# Charger_Board_3.net
KiCad netlist of a schematic drawn in EAGLE
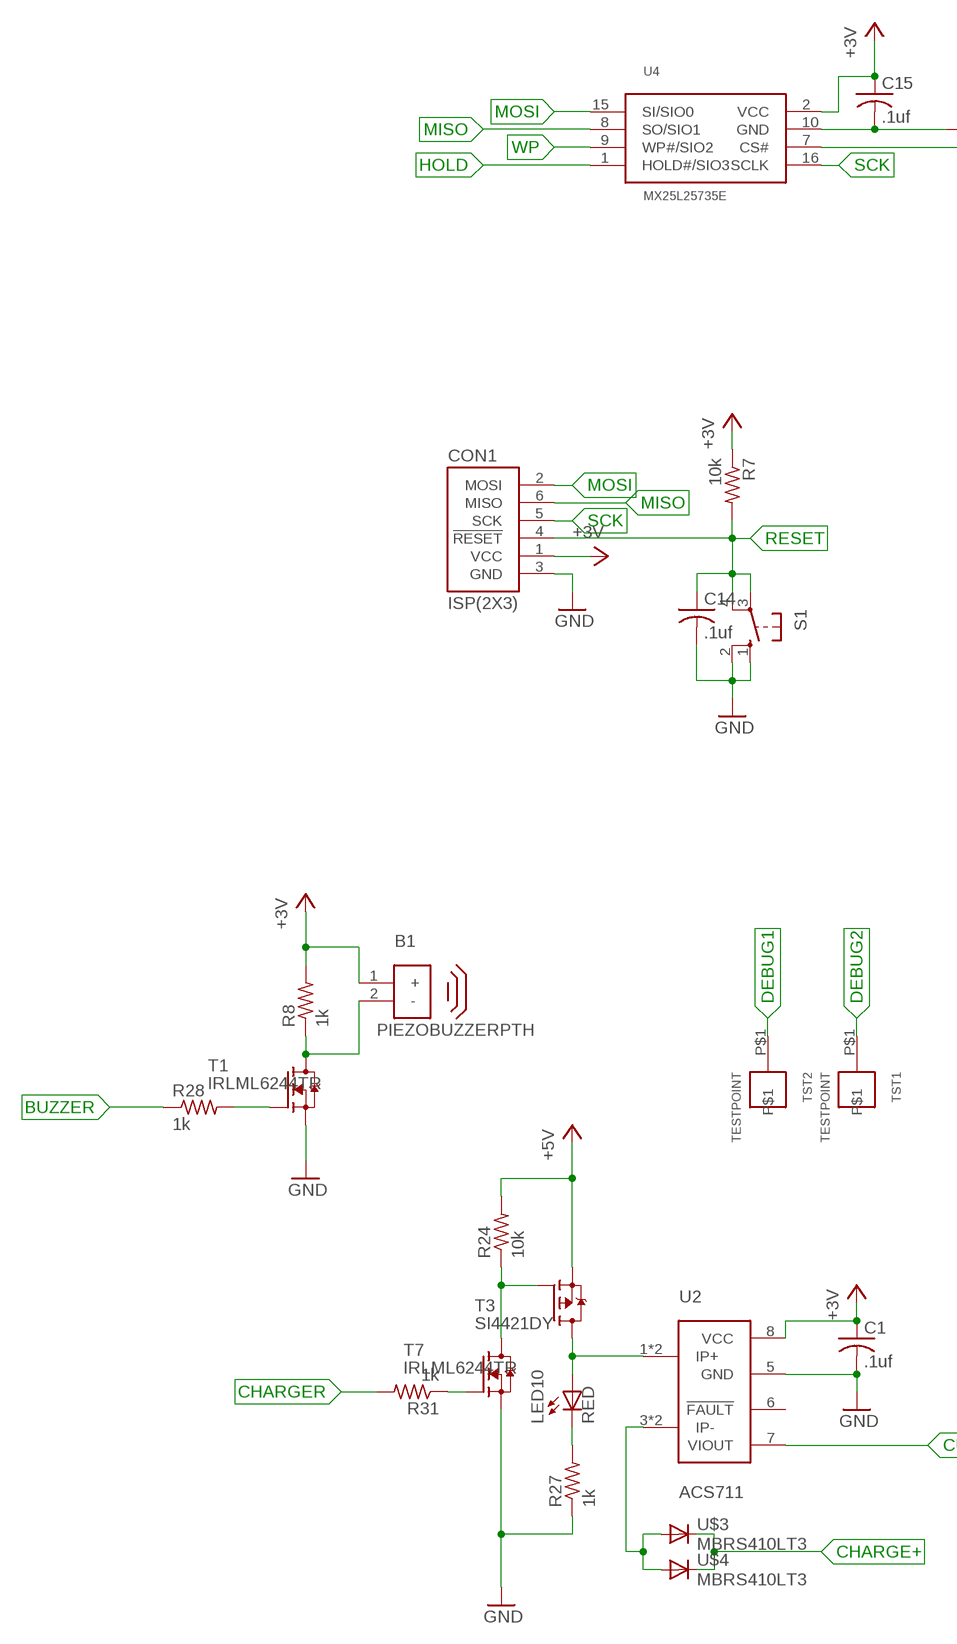
[diagram p0: schematic, sheet 1, part 1 of 2]
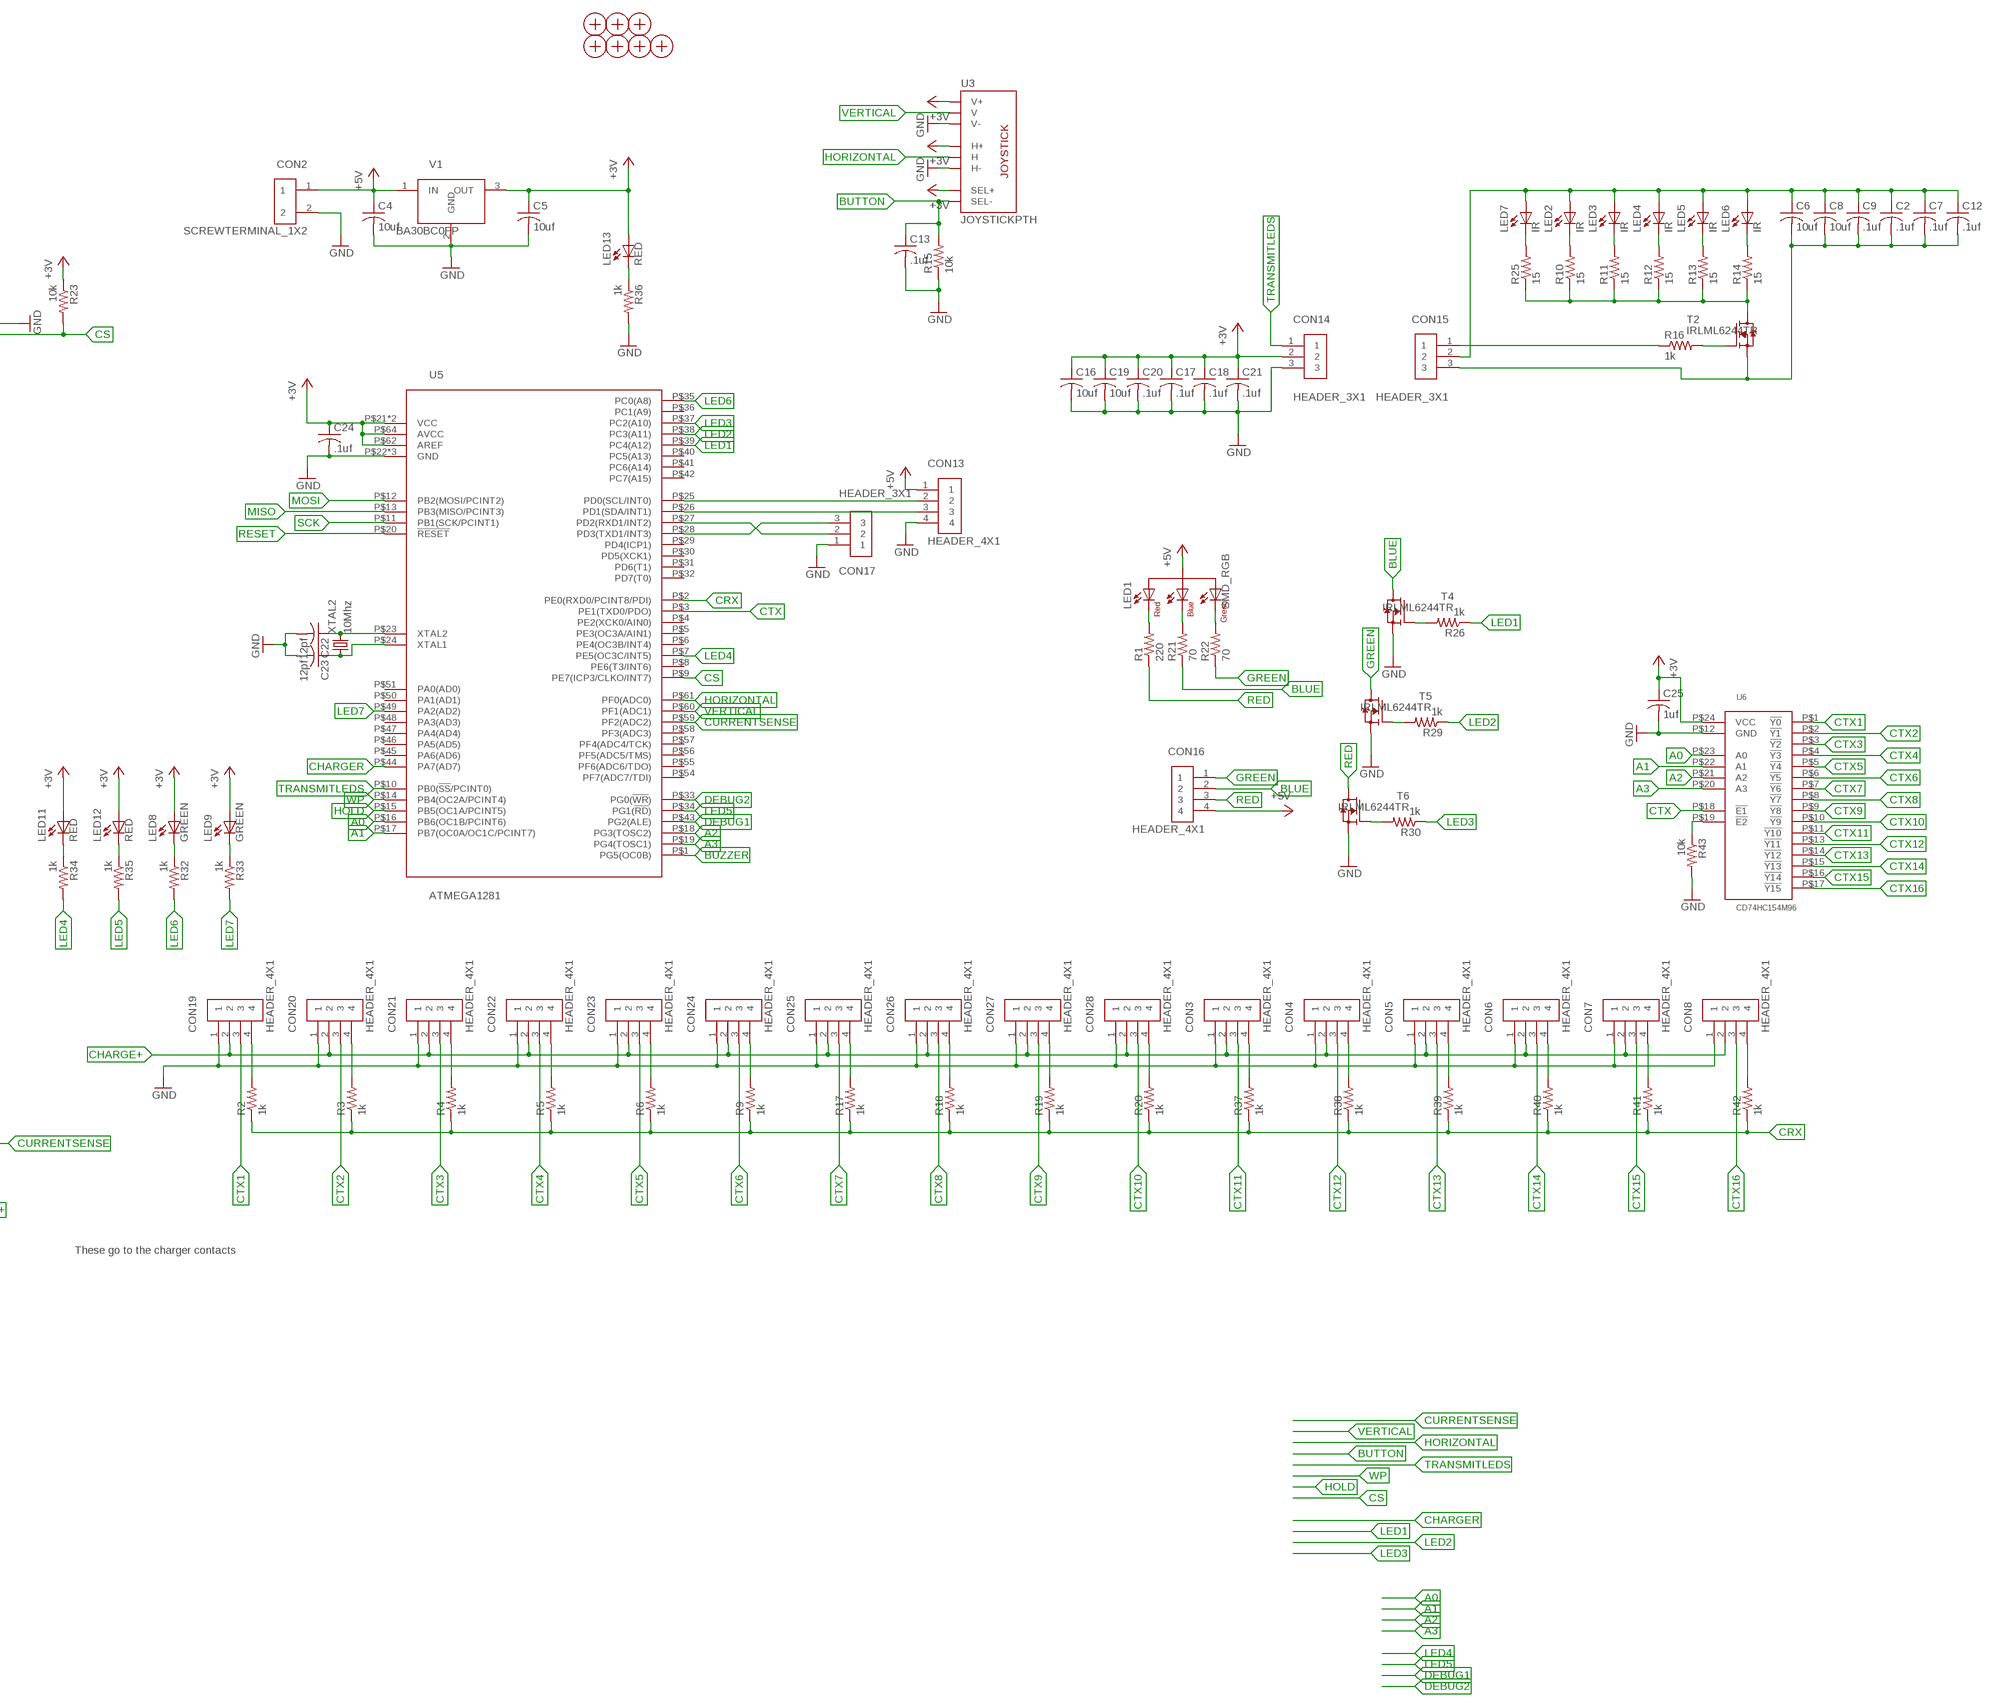
[diagram p1: schematic, sheet 1, part 2 of 2]

(export (version "E")
  (design (tool "Eeschema 10.0.6"))
  (components
    (comp (ref "B1")
      (value "PIEZOBUZZERPTH")
      (footprint "eagle-import:PIEZOBUZZER")
      (libsource (lib "eagle-import") (part "PIEZOBUZZERPTH"))
    )
    (comp (ref "C1")
      (value ".1uf")
      (footprint "eagle-import:0603")
      (libsource (lib "eagle-import") (part "CAP0603"))
    )
    (comp (ref "C2")
      (value ".1uf")
      (footprint "eagle-import:0603")
      (libsource (lib "eagle-import") (part "CAP0603"))
    )
    (comp (ref "C4")
      (value "10uf")
      (footprint "eagle-import:0805")
      (libsource (lib "eagle-import") (part "CAP0805"))
    )
    (comp (ref "C5")
      (value "10uf")
      (footprint "eagle-import:0805")
      (libsource (lib "eagle-import") (part "CAP0805"))
    )
    (comp (ref "C6")
      (value "10uf")
      (footprint "eagle-import:0805")
      (libsource (lib "eagle-import") (part "CAP0805"))
    )
    (comp (ref "C7")
      (value ".1uf")
      (footprint "eagle-import:0603")
      (libsource (lib "eagle-import") (part "CAP0603"))
    )
    (comp (ref "C8")
      (value "10uf")
      (footprint "eagle-import:0805")
      (libsource (lib "eagle-import") (part "CAP0805"))
    )
    (comp (ref "C9")
      (value ".1uf")
      (footprint "eagle-import:0603")
      (libsource (lib "eagle-import") (part "CAP0603"))
    )
    (comp (ref "C12")
      (value ".1uf")
      (footprint "eagle-import:0603")
      (libsource (lib "eagle-import") (part "CAP0603"))
    )
    (comp (ref "C13")
      (value ".1uf")
      (footprint "eagle-import:0603")
      (libsource (lib "eagle-import") (part "CAP0603"))
    )
    (comp (ref "C14")
      (value ".1uf")
      (footprint "eagle-import:0603")
      (libsource (lib "eagle-import") (part "CAP0603"))
    )
    (comp (ref "C15")
      (value ".1uf")
      (footprint "eagle-import:0603")
      (libsource (lib "eagle-import") (part "CAP0603"))
    )
    (comp (ref "C16")
      (value "10uf")
      (footprint "eagle-import:0805")
      (libsource (lib "eagle-import") (part "CAP0805"))
    )
    (comp (ref "C17")
      (value ".1uf")
      (footprint "eagle-import:0603")
      (libsource (lib "eagle-import") (part "CAP0603"))
    )
    (comp (ref "C18")
      (value ".1uf")
      (footprint "eagle-import:0603")
      (libsource (lib "eagle-import") (part "CAP0603"))
    )
    (comp (ref "C19")
      (value "10uf")
      (footprint "eagle-import:0805")
      (libsource (lib "eagle-import") (part "CAP0805"))
    )
    (comp (ref "C20")
      (value ".1uf")
      (footprint "eagle-import:0603")
      (libsource (lib "eagle-import") (part "CAP0603"))
    )
    (comp (ref "C21")
      (value ".1uf")
      (footprint "eagle-import:0603")
      (libsource (lib "eagle-import") (part "CAP0603"))
    )
    (comp (ref "C22")
      (value "12pf")
      (footprint "eagle-import:0603")
      (libsource (lib "eagle-import") (part "CAP0603"))
    )
    (comp (ref "C23")
      (value "12pf")
      (footprint "eagle-import:0603")
      (libsource (lib "eagle-import") (part "CAP0603"))
    )
    (comp (ref "C24")
      (value ".1uf")
      (footprint "eagle-import:0603")
      (libsource (lib "eagle-import") (part "CAP0603"))
    )
    (comp (ref "C25")
      (value "1uf")
      (footprint "eagle-import:0603")
      (libsource (lib "eagle-import") (part "CAP0603"))
    )
    (comp (ref "CON1")
      (value "ISP(2X3)")
      (footprint "eagle-import:PINHEADER(2X3)")
      (libsource (lib "eagle-import") (part "ISP(2X3)"))
    )
    (comp (ref "CON2")
      (value "SCREWTERMINAL_1X2")
      (footprint "eagle-import:SCREWTERMINAL_1X2")
      (libsource (lib "eagle-import") (part "SCREWTERMINAL_1X2"))
    )
    (comp (ref "CON3")
      (value "HEADER_4X1")
      (footprint "eagle-import:4PINHEADER_.100_")
      (libsource (lib "eagle-import") (part "HEADER_4X1"))
    )
    (comp (ref "CON4")
      (value "HEADER_4X1")
      (footprint "eagle-import:4PINHEADER_.100_")
      (libsource (lib "eagle-import") (part "HEADER_4X1"))
    )
    (comp (ref "CON5")
      (value "HEADER_4X1")
      (footprint "eagle-import:4PINHEADER_.100_")
      (libsource (lib "eagle-import") (part "HEADER_4X1"))
    )
    (comp (ref "CON6")
      (value "HEADER_4X1")
      (footprint "eagle-import:4PINHEADER_.100_")
      (libsource (lib "eagle-import") (part "HEADER_4X1"))
    )
    (comp (ref "CON7")
      (value "HEADER_4X1")
      (footprint "eagle-import:4PINHEADER_.100_")
      (libsource (lib "eagle-import") (part "HEADER_4X1"))
    )
    (comp (ref "CON8")
      (value "HEADER_4X1")
      (footprint "eagle-import:4PINHEADER_.100_")
      (libsource (lib "eagle-import") (part "HEADER_4X1"))
    )
    (comp (ref "CON13")
      (value "HEADER_4X1")
      (footprint "eagle-import:4PINHEADER_.100_")
      (libsource (lib "eagle-import") (part "HEADER_4X1"))
    )
    (comp (ref "CON14")
      (value "HEADER_3X1")
      (footprint "eagle-import:3PINHEADER_.100_")
      (libsource (lib "eagle-import") (part "HEADER_3X1"))
    )
    (comp (ref "CON15")
      (value "HEADER_3X1")
      (footprint "eagle-import:3PINHEADER_.100_")
      (libsource (lib "eagle-import") (part "HEADER_3X1"))
    )
    (comp (ref "CON16")
      (value "HEADER_4X1")
      (footprint "eagle-import:4PINHEADER_.100_")
      (libsource (lib "eagle-import") (part "HEADER_4X1"))
    )
    (comp (ref "CON17")
      (value "HEADER_3X1")
      (footprint "eagle-import:3PINHEADER_.100_")
      (libsource (lib "eagle-import") (part "HEADER_3X1"))
    )
    (comp (ref "CON19")
      (value "HEADER_4X1")
      (footprint "eagle-import:4PINHEADER_.100_")
      (libsource (lib "eagle-import") (part "HEADER_4X1"))
    )
    (comp (ref "CON20")
      (value "HEADER_4X1")
      (footprint "eagle-import:4PINHEADER_.100_")
      (libsource (lib "eagle-import") (part "HEADER_4X1"))
    )
    (comp (ref "CON21")
      (value "HEADER_4X1")
      (footprint "eagle-import:4PINHEADER_.100_")
      (libsource (lib "eagle-import") (part "HEADER_4X1"))
    )
    (comp (ref "CON22")
      (value "HEADER_4X1")
      (footprint "eagle-import:4PINHEADER_.100_")
      (libsource (lib "eagle-import") (part "HEADER_4X1"))
    )
    (comp (ref "CON23")
      (value "HEADER_4X1")
      (footprint "eagle-import:4PINHEADER_.100_")
      (libsource (lib "eagle-import") (part "HEADER_4X1"))
    )
    (comp (ref "CON24")
      (value "HEADER_4X1")
      (footprint "eagle-import:4PINHEADER_.100_")
      (libsource (lib "eagle-import") (part "HEADER_4X1"))
    )
    (comp (ref "CON25")
      (value "HEADER_4X1")
      (footprint "eagle-import:4PINHEADER_.100_")
      (libsource (lib "eagle-import") (part "HEADER_4X1"))
    )
    (comp (ref "CON26")
      (value "HEADER_4X1")
      (footprint "eagle-import:4PINHEADER_.100_")
      (libsource (lib "eagle-import") (part "HEADER_4X1"))
    )
    (comp (ref "CON27")
      (value "HEADER_4X1")
      (footprint "eagle-import:4PINHEADER_.100_")
      (libsource (lib "eagle-import") (part "HEADER_4X1"))
    )
    (comp (ref "CON28")
      (value "HEADER_4X1")
      (footprint "eagle-import:4PINHEADER_.100_")
      (libsource (lib "eagle-import") (part "HEADER_4X1"))
    )
    (comp (ref "H1")
      (value "MOUNTINGHOLE")
      (footprint "eagle-import:MOUNTINGHOLE")
      (libsource (lib "eagle-import") (part "MOUNTINGHOLE"))
    )
    (comp (ref "H2")
      (value "MOUNTINGHOLE")
      (footprint "eagle-import:MOUNTINGHOLE")
      (libsource (lib "eagle-import") (part "MOUNTINGHOLE"))
    )
    (comp (ref "H3")
      (value "MOUNTINGHOLE")
      (footprint "eagle-import:MOUNTINGHOLE")
      (libsource (lib "eagle-import") (part "MOUNTINGHOLE"))
    )
    (comp (ref "H4")
      (value "MOUNTINGHOLE")
      (footprint "eagle-import:MOUNTINGHOLE")
      (libsource (lib "eagle-import") (part "MOUNTINGHOLE"))
    )
    (comp (ref "H5")
      (value "MOUNTINGHOLE")
      (footprint "eagle-import:MOUNTINGHOLE")
      (libsource (lib "eagle-import") (part "MOUNTINGHOLE"))
    )
    (comp (ref "H6")
      (value "MOUNTINGHOLE")
      (footprint "eagle-import:MOUNTINGHOLE")
      (libsource (lib "eagle-import") (part "MOUNTINGHOLE"))
    )
    (comp (ref "H7")
      (value "MOUNTINGHOLE")
      (footprint "eagle-import:MOUNTINGHOLE")
      (libsource (lib "eagle-import") (part "MOUNTINGHOLE"))
    )
    (comp (ref "LED1")
      (value "SMD_RGB")
      (footprint "eagle-import:PLCC4")
      (libsource (lib "eagle-import") (part "SMD_RGB"))
    )
    (comp (ref "LED2")
      (value "IR")
      (footprint "eagle-import:5MM_LED_RA")
      (libsource (lib "eagle-import") (part "LED5MMRA"))
    )
    (comp (ref "LED3")
      (value "IR")
      (footprint "eagle-import:5MM_LED_RA")
      (libsource (lib "eagle-import") (part "LED5MMRA"))
    )
    (comp (ref "LED4")
      (value "IR")
      (footprint "eagle-import:5MM_LED_RA")
      (libsource (lib "eagle-import") (part "LED5MMRA"))
    )
    (comp (ref "LED5")
      (value "IR")
      (footprint "eagle-import:5MM_LED_RA")
      (libsource (lib "eagle-import") (part "LED5MMRA"))
    )
    (comp (ref "LED6")
      (value "IR")
      (footprint "eagle-import:5MM_LED_RA")
      (libsource (lib "eagle-import") (part "LED5MMRA"))
    )
    (comp (ref "LED7")
      (value "IR")
      (footprint "eagle-import:5MM_LED_RA")
      (libsource (lib "eagle-import") (part "LED5MMRA"))
    )
    (comp (ref "LED8")
      (value "GREEN")
      (footprint "eagle-import:LED0603")
      (libsource (lib "eagle-import") (part "LED0603"))
    )
    (comp (ref "LED9")
      (value "GREEN")
      (footprint "eagle-import:LED0603")
      (libsource (lib "eagle-import") (part "LED0603"))
    )
    (comp (ref "LED10")
      (value "RED")
      (footprint "eagle-import:LED0603")
      (libsource (lib "eagle-import") (part "LED0603"))
    )
    (comp (ref "LED11")
      (value "RED")
      (footprint "eagle-import:LED0603")
      (libsource (lib "eagle-import") (part "LED0603"))
    )
    (comp (ref "LED12")
      (value "RED")
      (footprint "eagle-import:LED0603")
      (libsource (lib "eagle-import") (part "LED0603"))
    )
    (comp (ref "LED13")
      (value "RED")
      (footprint "eagle-import:LED0603")
      (libsource (lib "eagle-import") (part "LED0603"))
    )
    (comp (ref "R1")
      (value "220")
      (footprint "eagle-import:0603")
      (libsource (lib "eagle-import") (part "RES0603"))
    )
    (comp (ref "R2")
      (value "1k")
      (footprint "eagle-import:0603")
      (libsource (lib "eagle-import") (part "RES0603"))
    )
    (comp (ref "R3")
      (value "1k")
      (footprint "eagle-import:0603")
      (libsource (lib "eagle-import") (part "RES0603"))
    )
    (comp (ref "R4")
      (value "1k")
      (footprint "eagle-import:0603")
      (libsource (lib "eagle-import") (part "RES0603"))
    )
    (comp (ref "R5")
      (value "1k")
      (footprint "eagle-import:0603")
      (libsource (lib "eagle-import") (part "RES0603"))
    )
    (comp (ref "R6")
      (value "1k")
      (footprint "eagle-import:0603")
      (libsource (lib "eagle-import") (part "RES0603"))
    )
    (comp (ref "R7")
      (value "10k")
      (footprint "eagle-import:0603")
      (libsource (lib "eagle-import") (part "RES0603"))
    )
    (comp (ref "R8")
      (value "1k")
      (footprint "eagle-import:0603")
      (libsource (lib "eagle-import") (part "RES0603"))
    )
    (comp (ref "R9")
      (value "1k")
      (footprint "eagle-import:0603")
      (libsource (lib "eagle-import") (part "RES0603"))
    )
    (comp (ref "R10")
      (value "15")
      (footprint "eagle-import:0603")
      (libsource (lib "eagle-import") (part "RES0603"))
    )
    (comp (ref "R11")
      (value "15")
      (footprint "eagle-import:0603")
      (libsource (lib "eagle-import") (part "RES0603"))
    )
    (comp (ref "R12")
      (value "15")
      (footprint "eagle-import:0603")
      (libsource (lib "eagle-import") (part "RES0603"))
    )
    (comp (ref "R13")
      (value "15")
      (footprint "eagle-import:0603")
      (libsource (lib "eagle-import") (part "RES0603"))
    )
    (comp (ref "R14")
      (value "15")
      (footprint "eagle-import:0603")
      (libsource (lib "eagle-import") (part "RES0603"))
    )
    (comp (ref "R15")
      (value "10k")
      (footprint "eagle-import:0603")
      (libsource (lib "eagle-import") (part "RES0603"))
    )
    (comp (ref "R16")
      (value "1k")
      (footprint "eagle-import:0603")
      (libsource (lib "eagle-import") (part "RES0603"))
    )
    (comp (ref "R17")
      (value "1k")
      (footprint "eagle-import:0603")
      (libsource (lib "eagle-import") (part "RES0603"))
    )
    (comp (ref "R18")
      (value "1k")
      (footprint "eagle-import:0603")
      (libsource (lib "eagle-import") (part "RES0603"))
    )
    (comp (ref "R19")
      (value "1k")
      (footprint "eagle-import:0603")
      (libsource (lib "eagle-import") (part "RES0603"))
    )
    (comp (ref "R20")
      (value "1k")
      (footprint "eagle-import:0603")
      (libsource (lib "eagle-import") (part "RES0603"))
    )
    (comp (ref "R21")
      (value "70")
      (footprint "eagle-import:0603")
      (libsource (lib "eagle-import") (part "RES0603"))
    )
    (comp (ref "R22")
      (value "70")
      (footprint "eagle-import:0603")
      (libsource (lib "eagle-import") (part "RES0603"))
    )
    (comp (ref "R23")
      (value "10k")
      (footprint "eagle-import:0603")
      (libsource (lib "eagle-import") (part "RES0603"))
    )
    (comp (ref "R24")
      (value "10k")
      (footprint "eagle-import:0603")
      (libsource (lib "eagle-import") (part "RES0603"))
    )
    (comp (ref "R25")
      (value "15")
      (footprint "eagle-import:0603")
      (libsource (lib "eagle-import") (part "RES0603"))
    )
    (comp (ref "R26")
      (value "1k")
      (footprint "eagle-import:0603")
      (libsource (lib "eagle-import") (part "RES0603"))
    )
    (comp (ref "R27")
      (value "1k")
      (footprint "eagle-import:0603")
      (libsource (lib "eagle-import") (part "RES0603"))
    )
    (comp (ref "R28")
      (value "1k")
      (footprint "eagle-import:0603")
      (libsource (lib "eagle-import") (part "RES0603"))
    )
    (comp (ref "R29")
      (value "1k")
      (footprint "eagle-import:0603")
      (libsource (lib "eagle-import") (part "RES0603"))
    )
    (comp (ref "R30")
      (value "1k")
      (footprint "eagle-import:0603")
      (libsource (lib "eagle-import") (part "RES0603"))
    )
    (comp (ref "R31")
      (value "1k")
      (footprint "eagle-import:0603")
      (libsource (lib "eagle-import") (part "RES0603"))
    )
    (comp (ref "R32")
      (value "1k")
      (footprint "eagle-import:0603")
      (libsource (lib "eagle-import") (part "RES0603"))
    )
    (comp (ref "R33")
      (value "1k")
      (footprint "eagle-import:0603")
      (libsource (lib "eagle-import") (part "RES0603"))
    )
    (comp (ref "R34")
      (value "1k")
      (footprint "eagle-import:0603")
      (libsource (lib "eagle-import") (part "RES0603"))
    )
    (comp (ref "R35")
      (value "1k")
      (footprint "eagle-import:0603")
      (libsource (lib "eagle-import") (part "RES0603"))
    )
    (comp (ref "R36")
      (value "1k")
      (footprint "eagle-import:0603")
      (libsource (lib "eagle-import") (part "RES0603"))
    )
    (comp (ref "R37")
      (value "1k")
      (footprint "eagle-import:0603")
      (libsource (lib "eagle-import") (part "RES0603"))
    )
    (comp (ref "R38")
      (value "1k")
      (footprint "eagle-import:0603")
      (libsource (lib "eagle-import") (part "RES0603"))
    )
    (comp (ref "R39")
      (value "1k")
      (footprint "eagle-import:0603")
      (libsource (lib "eagle-import") (part "RES0603"))
    )
    (comp (ref "R40")
      (value "1k")
      (footprint "eagle-import:0603")
      (libsource (lib "eagle-import") (part "RES0603"))
    )
    (comp (ref "R41")
      (value "1k")
      (footprint "eagle-import:0603")
      (libsource (lib "eagle-import") (part "RES0603"))
    )
    (comp (ref "R42")
      (value "1k")
      (footprint "eagle-import:0603")
      (libsource (lib "eagle-import") (part "RES0603"))
    )
    (comp (ref "R43")
      (value "10k")
      (footprint "eagle-import:0603")
      (libsource (lib "eagle-import") (part "RES0603"))
    )
    (comp (ref "S1")
      (value "10-XX")
      (footprint "eagle-import:B3F-10XX")
      (fields (field (name "MPN") "B3F-1000"))
      (libsource (lib "eagle-import") (part "10-XX"))
    )
    (comp (ref "T1")
      (value "IRLML6244TR")
      (footprint "eagle-import:SOT23")
      (libsource (lib "eagle-import") (part "IRLML6244TR"))
    )
    (comp (ref "T2")
      (value "IRLML6244TR")
      (footprint "eagle-import:SOT23")
      (libsource (lib "eagle-import") (part "IRLML6244TR"))
    )
    (comp (ref "T3")
      (value "SI4421DY")
      (footprint "eagle-import:S0-8")
      (libsource (lib "eagle-import") (part "SI4421DY"))
    )
    (comp (ref "T4")
      (value "IRLML6244TR")
      (footprint "eagle-import:SOT23")
      (libsource (lib "eagle-import") (part "IRLML6244TR"))
    )
    (comp (ref "T5")
      (value "IRLML6244TR")
      (footprint "eagle-import:SOT23")
      (libsource (lib "eagle-import") (part "IRLML6244TR"))
    )
    (comp (ref "T6")
      (value "IRLML6244TR")
      (footprint "eagle-import:SOT23")
      (libsource (lib "eagle-import") (part "IRLML6244TR"))
    )
    (comp (ref "T7")
      (value "IRLML6244TR")
      (footprint "eagle-import:SOT23")
      (libsource (lib "eagle-import") (part "IRLML6244TR"))
    )
    (comp (ref "TST1")
      (value "TESTPOINT")
      (footprint "eagle-import:TESTPOINT")
      (libsource (lib "eagle-import") (part "TESTPOINT"))
    )
    (comp (ref "TST2")
      (value "TESTPOINT")
      (footprint "eagle-import:TESTPOINT")
      (libsource (lib "eagle-import") (part "TESTPOINT"))
    )
    (comp (ref "U$3")
      (value "MBRS410LT3")
      (footprint "eagle-import:SMD_DIODE")
      (libsource (lib "eagle-import") (part "MBRS410LT3"))
    )
    (comp (ref "U$4")
      (value "MBRS410LT3")
      (footprint "eagle-import:SMD_DIODE")
      (libsource (lib "eagle-import") (part "MBRS410LT3"))
    )
    (comp (ref "U2")
      (value "ACS711")
      (footprint "eagle-import:8SOIC")
      (libsource (lib "eagle-import") (part "ACS711"))
    )
    (comp (ref "U3")
      (value "JOYSTICKPTH")
      (footprint "eagle-import:JOYSTICK")
      (libsource (lib "eagle-import") (part "JOYSTICKPTH"))
    )
    (comp (ref "U4")
      (value "MX25L25735E")
      (footprint "eagle-import:SOIC16R")
      (libsource (lib "eagle-import") (part "MX25L25735E"))
    )
    (comp (ref "U5")
      (value "ATMEGA1281")
      (footprint "eagle-import:TQFP64")
      (libsource (lib "eagle-import") (part "ATMEGA1281"))
    )
    (comp (ref "U6")
      (value "CD74HC154M96")
      (footprint "eagle-import:24SOIC")
      (libsource (lib "eagle-import") (part "CD74HC154M96"))
    )
    (comp (ref "V1")
      (value "BA30BC0FP")
      (footprint "eagle-import:DPAK")
      (libsource (lib "eagle-import") (part "BA30BC0FP"))
    )
    (comp (ref "XTAL2")
      (value "10Mhz")
      (footprint "eagle-import:SMDXTAL")
      (libsource (lib "eagle-import") (part "NX5032GA-10.000000MHZ"))
    )
  )
  (nets
    (net (code "1") (name "+3V") (class "Default")
      (node (ref "B1") (pin "1") (pinfunction "+_1") (pintype "bidirectional"))
      (node (ref "C1") (pin "1") (pinfunction "1_1") (pintype "passive"))
      (node (ref "C15") (pin "1") (pinfunction "1_1") (pintype "passive"))
      (node (ref "C16") (pin "1") (pinfunction "1_1") (pintype "passive"))
      (node (ref "C17") (pin "1") (pinfunction "1_1") (pintype "passive"))
      (node (ref "C18") (pin "1") (pinfunction "1_1") (pintype "passive"))
      (node (ref "C19") (pin "1") (pinfunction "1_1") (pintype "passive"))
      (node (ref "C20") (pin "1") (pinfunction "1_1") (pintype "passive"))
      (node (ref "C21") (pin "1") (pinfunction "1_1") (pintype "passive"))
      (node (ref "C24") (pin "1") (pinfunction "1_1") (pintype "passive"))
      (node (ref "C25") (pin "1") (pinfunction "1_1") (pintype "passive"))
      (node (ref "C5") (pin "1") (pinfunction "1_1") (pintype "passive"))
      (node (ref "CON1") (pin "1") (pinfunction "VCC_1") (pintype "bidirectional"))
      (node (ref "CON14") (pin "2") (pinfunction "2_2") (pintype "bidirectional"))
      (node (ref "LED11") (pin "2") (pinfunction "A_2") (pintype "passive"))
      (node (ref "LED12") (pin "2") (pinfunction "A_2") (pintype "passive"))
      (node (ref "LED13") (pin "2") (pinfunction "A_2") (pintype "passive"))
      (node (ref "LED8") (pin "2") (pinfunction "A_2") (pintype "passive"))
      (node (ref "LED9") (pin "2") (pinfunction "A_2") (pintype "passive"))
      (node (ref "R23") (pin "1") (pinfunction "1_1") (pintype "passive"))
      (node (ref "R7") (pin "1") (pinfunction "1_1") (pintype "passive"))
      (node (ref "R8") (pin "2") (pinfunction "2_2") (pintype "passive"))
      (node (ref "U2") (pin "8") (pinfunction "VCC_8") (pintype "bidirectional"))
      (node (ref "U3") (pin "B1A") (pinfunction "SEL+_B1A") (pintype "bidirectional"))
      (node (ref "U3") (pin "H1") (pinfunction "H+_H1") (pintype "bidirectional"))
      (node (ref "U3") (pin "V1") (pinfunction "V+_V1") (pintype "bidirectional"))
      (node (ref "U4") (pin "2") (pinfunction "VCC_2") (pintype "bidirectional"))
      (node (ref "U5") (pin "P$21") (pinfunction "VCC_P$21") (pintype "bidirectional"))
      (node (ref "U5") (pin "P$52") (pinfunction "VCC_P$52") (pintype "bidirectional"))
      (node (ref "U5") (pin "P$62") (pinfunction "AREF_P$62") (pintype "bidirectional"))
      (node (ref "U5") (pin "P$64") (pinfunction "AVCC_P$64") (pintype "bidirectional"))
      (node (ref "U6") (pin "P$24") (pinfunction "VCC_P$24") (pintype "bidirectional"))
      (node (ref "V1") (pin "3") (pinfunction "OUT_3") (pintype "bidirectional"))
    )
    (net (code "2") (name "+5V") (class "Default")
      (node (ref "C4") (pin "1") (pinfunction "1_1") (pintype "passive"))
      (node (ref "CON13") (pin "1") (pinfunction "1_1") (pintype "bidirectional"))
      (node (ref "CON16") (pin "4") (pinfunction "4_4") (pintype "bidirectional"))
      (node (ref "CON2") (pin "1") (pinfunction "1_1") (pintype "bidirectional"))
      (node (ref "LED1") (pin "2") (pinfunction "COMMONANODE_2") (pintype "passive"))
      (node (ref "R24") (pin "2") (pinfunction "2_2") (pintype "passive"))
      (node (ref "T3") (pin "1") (pinfunction "S_1") (pintype "passive"))
      (node (ref "T3") (pin "2") (pinfunction "S_2") (pintype "passive"))
      (node (ref "T3") (pin "3") (pinfunction "S_3") (pintype "passive"))
      (node (ref "V1") (pin "1") (pinfunction "IN_1") (pintype "bidirectional"))
    )
    (net (code "3") (name "A0") (class "Default")
      (node (ref "U5") (pin "P$16") (pinfunction "PB6(OC1B/PCINT6)_P$16") (pintype "bidirectional"))
      (node (ref "U6") (pin "P$23") (pinfunction "A0_P$23") (pintype "bidirectional"))
    )
    (net (code "4") (name "A1") (class "Default")
      (node (ref "U5") (pin "P$17") (pinfunction "PB7(OC0A/OC1C/PCINT7)_P$17") (pintype "bidirectional"))
      (node (ref "U6") (pin "P$22") (pinfunction "A1_P$22") (pintype "bidirectional"))
    )
    (net (code "5") (name "A2") (class "Default")
      (node (ref "U5") (pin "P$18") (pinfunction "PG3(TOSC2)_P$18") (pintype "bidirectional"))
      (node (ref "U6") (pin "P$21") (pinfunction "A2_P$21") (pintype "bidirectional"))
    )
    (net (code "6") (name "A3") (class "Default")
      (node (ref "U5") (pin "P$19") (pinfunction "PG4(TOSC1)_P$19") (pintype "bidirectional"))
      (node (ref "U6") (pin "P$20") (pinfunction "A3_P$20") (pintype "bidirectional"))
    )
    (net (code "7") (name "BLUE") (class "Default")
      (node (ref "CON16") (pin "2") (pinfunction "2_2") (pintype "bidirectional"))
      (node (ref "R21") (pin "1") (pinfunction "1_1") (pintype "passive"))
      (node (ref "T4") (pin "3") (pinfunction "D_3") (pintype "passive"))
    )
    (net (code "8") (name "BUTTON") (class "Default")
      (node (ref "C13") (pin "1") (pinfunction "1_1") (pintype "passive"))
      (node (ref "R15") (pin "2") (pinfunction "2_2") (pintype "passive"))
      (node (ref "U3") (pin "B2A") (pinfunction "SEL-_B2A") (pintype "bidirectional"))
    )
    (net (code "9") (name "BUZZER") (class "Default")
      (node (ref "R28") (pin "1") (pinfunction "1_1") (pintype "passive"))
      (node (ref "U5") (pin "P$1") (pinfunction "PG5(OC0B)_P$1") (pintype "bidirectional"))
    )
    (net (code "10") (name "CHARGE+") (class "Default")
      (node (ref "CON19") (pin "2") (pinfunction "2_2") (pintype "bidirectional"))
      (node (ref "CON20") (pin "2") (pinfunction "2_2") (pintype "bidirectional"))
      (node (ref "CON21") (pin "2") (pinfunction "2_2") (pintype "bidirectional"))
      (node (ref "CON22") (pin "2") (pinfunction "2_2") (pintype "bidirectional"))
      (node (ref "CON23") (pin "2") (pinfunction "2_2") (pintype "bidirectional"))
      (node (ref "CON24") (pin "2") (pinfunction "2_2") (pintype "bidirectional"))
      (node (ref "CON25") (pin "2") (pinfunction "2_2") (pintype "bidirectional"))
      (node (ref "CON26") (pin "2") (pinfunction "2_2") (pintype "bidirectional"))
      (node (ref "CON27") (pin "2") (pinfunction "2_2") (pintype "bidirectional"))
      (node (ref "CON28") (pin "2") (pinfunction "2_2") (pintype "bidirectional"))
      (node (ref "CON3") (pin "2") (pinfunction "2_2") (pintype "bidirectional"))
      (node (ref "CON4") (pin "2") (pinfunction "2_2") (pintype "bidirectional"))
      (node (ref "CON5") (pin "2") (pinfunction "2_2") (pintype "bidirectional"))
      (node (ref "CON6") (pin "2") (pinfunction "2_2") (pintype "bidirectional"))
      (node (ref "CON7") (pin "2") (pinfunction "2_2") (pintype "bidirectional"))
      (node (ref "CON8") (pin "2") (pinfunction "2_2") (pintype "bidirectional"))
      (node (ref "U$3") (pin "2") (pinfunction "C_2") (pintype "passive"))
      (node (ref "U$4") (pin "2") (pinfunction "C_2") (pintype "passive"))
    )
    (net (code "11") (name "CHARGER") (class "Default")
      (node (ref "R31") (pin "2") (pinfunction "2_2") (pintype "passive"))
      (node (ref "U5") (pin "P$44") (pinfunction "PA7(AD7)_P$44") (pintype "bidirectional"))
    )
    (net (code "12") (name "CRX") (class "Default")
      (node (ref "R17") (pin "1") (pinfunction "1_1") (pintype "passive"))
      (node (ref "R18") (pin "1") (pinfunction "1_1") (pintype "passive"))
      (node (ref "R19") (pin "1") (pinfunction "1_1") (pintype "passive"))
      (node (ref "R2") (pin "1") (pinfunction "1_1") (pintype "passive"))
      (node (ref "R20") (pin "1") (pinfunction "1_1") (pintype "passive"))
      (node (ref "R3") (pin "1") (pinfunction "1_1") (pintype "passive"))
      (node (ref "R37") (pin "1") (pinfunction "1_1") (pintype "passive"))
      (node (ref "R38") (pin "1") (pinfunction "1_1") (pintype "passive"))
      (node (ref "R39") (pin "1") (pinfunction "1_1") (pintype "passive"))
      (node (ref "R4") (pin "1") (pinfunction "1_1") (pintype "passive"))
      (node (ref "R40") (pin "1") (pinfunction "1_1") (pintype "passive"))
      (node (ref "R41") (pin "1") (pinfunction "1_1") (pintype "passive"))
      (node (ref "R42") (pin "1") (pinfunction "1_1") (pintype "passive"))
      (node (ref "R5") (pin "1") (pinfunction "1_1") (pintype "passive"))
      (node (ref "R6") (pin "1") (pinfunction "1_1") (pintype "passive"))
      (node (ref "R9") (pin "1") (pinfunction "1_1") (pintype "passive"))
      (node (ref "U5") (pin "P$2") (pinfunction "PE0(RXD0/PCINT8/PDI)_P$2") (pintype "bidirectional"))
    )
    (net (code "13") (name "CS") (class "Default")
      (node (ref "R23") (pin "2") (pinfunction "2_2") (pintype "passive"))
      (node (ref "U4") (pin "7") (pinfunction "CS#_7") (pintype "bidirectional"))
      (node (ref "U5") (pin "P$9") (pinfunction "PE7(ICP3/CLKO/INT7)_P$9") (pintype "bidirectional"))
    )
    (net (code "14") (name "CTX") (class "Default")
      (node (ref "U5") (pin "P$3") (pinfunction "PE1(TXD0/PDO)_P$3") (pintype "bidirectional"))
      (node (ref "U6") (pin "P$18") (pinfunction "~{E1}_P$18") (pintype "bidirectional"))
    )
    (net (code "15") (name "CTX1") (class "Default")
      (node (ref "CON19") (pin "3") (pinfunction "3_3") (pintype "bidirectional"))
      (node (ref "U6") (pin "P$1") (pinfunction "~{Y0}_P$1") (pintype "bidirectional"))
    )
    (net (code "16") (name "CTX2") (class "Default")
      (node (ref "CON20") (pin "3") (pinfunction "3_3") (pintype "bidirectional"))
      (node (ref "U6") (pin "P$2") (pinfunction "~{Y1}_P$2") (pintype "bidirectional"))
    )
    (net (code "17") (name "CTX3") (class "Default")
      (node (ref "CON21") (pin "3") (pinfunction "3_3") (pintype "bidirectional"))
      (node (ref "U6") (pin "P$3") (pinfunction "~{Y2}_P$3") (pintype "bidirectional"))
    )
    (net (code "18") (name "CTX4") (class "Default")
      (node (ref "CON22") (pin "3") (pinfunction "3_3") (pintype "bidirectional"))
      (node (ref "U6") (pin "P$4") (pinfunction "~{Y3}_P$4") (pintype "bidirectional"))
    )
    (net (code "19") (name "CTX5") (class "Default")
      (node (ref "CON23") (pin "3") (pinfunction "3_3") (pintype "bidirectional"))
      (node (ref "U6") (pin "P$5") (pinfunction "~{Y4}_P$5") (pintype "bidirectional"))
    )
    (net (code "20") (name "CTX6") (class "Default")
      (node (ref "CON24") (pin "3") (pinfunction "3_3") (pintype "bidirectional"))
      (node (ref "U6") (pin "P$6") (pinfunction "~{Y5}_P$6") (pintype "bidirectional"))
    )
    (net (code "21") (name "CTX7") (class "Default")
      (node (ref "CON25") (pin "3") (pinfunction "3_3") (pintype "bidirectional"))
      (node (ref "U6") (pin "P$7") (pinfunction "~{Y6}_P$7") (pintype "bidirectional"))
    )
    (net (code "22") (name "CTX8") (class "Default")
      (node (ref "CON26") (pin "3") (pinfunction "3_3") (pintype "bidirectional"))
      (node (ref "U6") (pin "P$8") (pinfunction "~{Y7}_P$8") (pintype "bidirectional"))
    )
    (net (code "23") (name "CTX9") (class "Default")
      (node (ref "CON27") (pin "3") (pinfunction "3_3") (pintype "bidirectional"))
      (node (ref "U6") (pin "P$9") (pinfunction "~{Y8}_P$9") (pintype "bidirectional"))
    )
    (net (code "24") (name "CTX10") (class "Default")
      (node (ref "CON28") (pin "3") (pinfunction "3_3") (pintype "bidirectional"))
      (node (ref "U6") (pin "P$10") (pinfunction "~{Y9}_P$10") (pintype "bidirectional"))
    )
    (net (code "25") (name "CTX11") (class "Default")
      (node (ref "CON3") (pin "3") (pinfunction "3_3") (pintype "bidirectional"))
      (node (ref "U6") (pin "P$11") (pinfunction "~{Y10}_P$11") (pintype "bidirectional"))
    )
    (net (code "26") (name "CTX12") (class "Default")
      (node (ref "CON4") (pin "3") (pinfunction "3_3") (pintype "bidirectional"))
      (node (ref "U6") (pin "P$13") (pinfunction "~{Y11}_P$13") (pintype "bidirectional"))
    )
    (net (code "27") (name "CTX13") (class "Default")
      (node (ref "CON5") (pin "3") (pinfunction "3_3") (pintype "bidirectional"))
      (node (ref "U6") (pin "P$14") (pinfunction "~{Y12}_P$14") (pintype "bidirectional"))
    )
    (net (code "28") (name "CTX14") (class "Default")
      (node (ref "CON6") (pin "3") (pinfunction "3_3") (pintype "bidirectional"))
      (node (ref "U6") (pin "P$15") (pinfunction "~{Y13}_P$15") (pintype "bidirectional"))
    )
    (net (code "29") (name "CTX15") (class "Default")
      (node (ref "CON7") (pin "3") (pinfunction "3_3") (pintype "bidirectional"))
      (node (ref "U6") (pin "P$16") (pinfunction "~{Y14}_P$16") (pintype "bidirectional"))
    )
    (net (code "30") (name "CTX16") (class "Default")
      (node (ref "CON8") (pin "3") (pinfunction "3_3") (pintype "bidirectional"))
      (node (ref "U6") (pin "P$17") (pinfunction "~{Y15}_P$17") (pintype "bidirectional"))
    )
    (net (code "31") (name "CURRENTSENSE") (class "Default")
      (node (ref "U2") (pin "7") (pinfunction "VIOUT_7") (pintype "bidirectional"))
      (node (ref "U5") (pin "P$59") (pinfunction "PF2(ADC2)_P$59") (pintype "bidirectional"))
    )
    (net (code "32") (name "DEBUG1") (class "Default")
      (node (ref "TST2") (pin "P$1") (pinfunction "P$1_P$1") (pintype "bidirectional"))
      (node (ref "U5") (pin "P$43") (pinfunction "PG2(ALE)_P$43") (pintype "bidirectional"))
    )
    (net (code "33") (name "DEBUG2") (class "Default")
      (node (ref "TST1") (pin "P$1") (pinfunction "P$1_P$1") (pintype "bidirectional"))
      (node (ref "U5") (pin "P$33") (pinfunction "PG0(~{WR})_P$33") (pintype "bidirectional"))
    )
    (net (code "34") (name "GND") (class "Default")
      (node (ref "C1") (pin "2") (pinfunction "2_2") (pintype "passive"))
      (node (ref "C13") (pin "2") (pinfunction "2_2") (pintype "passive"))
      (node (ref "C14") (pin "2") (pinfunction "2_2") (pintype "passive"))
      (node (ref "C15") (pin "2") (pinfunction "2_2") (pintype "passive"))
      (node (ref "C16") (pin "2") (pinfunction "2_2") (pintype "passive"))
      (node (ref "C17") (pin "2") (pinfunction "2_2") (pintype "passive"))
      (node (ref "C18") (pin "2") (pinfunction "2_2") (pintype "passive"))
      (node (ref "C19") (pin "2") (pinfunction "2_2") (pintype "passive"))
      (node (ref "C20") (pin "2") (pinfunction "2_2") (pintype "passive"))
      (node (ref "C21") (pin "2") (pinfunction "2_2") (pintype "passive"))
      (node (ref "C22") (pin "2") (pinfunction "2_2") (pintype "passive"))
      (node (ref "C23") (pin "2") (pinfunction "2_2") (pintype "passive"))
      (node (ref "C24") (pin "2") (pinfunction "2_2") (pintype "passive"))
      (node (ref "C25") (pin "2") (pinfunction "2_2") (pintype "passive"))
      (node (ref "C4") (pin "2") (pinfunction "2_2") (pintype "passive"))
      (node (ref "C5") (pin "2") (pinfunction "2_2") (pintype "passive"))
      (node (ref "CON1") (pin "3") (pinfunction "GND_3") (pintype "bidirectional"))
      (node (ref "CON13") (pin "4") (pinfunction "4_4") (pintype "bidirectional"))
      (node (ref "CON14") (pin "3") (pinfunction "3_3") (pintype "bidirectional"))
      (node (ref "CON17") (pin "1") (pinfunction "1_1") (pintype "bidirectional"))
      (node (ref "CON19") (pin "1") (pinfunction "1_1") (pintype "bidirectional"))
      (node (ref "CON2") (pin "2") (pinfunction "2_2") (pintype "bidirectional"))
      (node (ref "CON20") (pin "1") (pinfunction "1_1") (pintype "bidirectional"))
      (node (ref "CON21") (pin "1") (pinfunction "1_1") (pintype "bidirectional"))
      (node (ref "CON22") (pin "1") (pinfunction "1_1") (pintype "bidirectional"))
      (node (ref "CON23") (pin "1") (pinfunction "1_1") (pintype "bidirectional"))
      (node (ref "CON24") (pin "1") (pinfunction "1_1") (pintype "bidirectional"))
      (node (ref "CON25") (pin "1") (pinfunction "1_1") (pintype "bidirectional"))
      (node (ref "CON26") (pin "1") (pinfunction "1_1") (pintype "bidirectional"))
      (node (ref "CON27") (pin "1") (pinfunction "1_1") (pintype "bidirectional"))
      (node (ref "CON28") (pin "1") (pinfunction "1_1") (pintype "bidirectional"))
      (node (ref "CON3") (pin "1") (pinfunction "1_1") (pintype "bidirectional"))
      (node (ref "CON4") (pin "1") (pinfunction "1_1") (pintype "bidirectional"))
      (node (ref "CON5") (pin "1") (pinfunction "1_1") (pintype "bidirectional"))
      (node (ref "CON6") (pin "1") (pinfunction "1_1") (pintype "bidirectional"))
      (node (ref "CON7") (pin "1") (pinfunction "1_1") (pintype "bidirectional"))
      (node (ref "CON8") (pin "1") (pinfunction "1_1") (pintype "bidirectional"))
      (node (ref "R15") (pin "1") (pinfunction "1_1") (pintype "passive"))
      (node (ref "R27") (pin "1") (pinfunction "1_1") (pintype "passive"))
      (node (ref "R36") (pin "2") (pinfunction "2_2") (pintype "passive"))
      (node (ref "R43") (pin "2") (pinfunction "2_2") (pintype "passive"))
      (node (ref "S1") (pin "1") (pinfunction "S_1") (pintype "passive"))
      (node (ref "S1") (pin "2") (pinfunction "S1_2") (pintype "passive"))
      (node (ref "T1") (pin "2") (pinfunction "S_2") (pintype "passive"))
      (node (ref "T4") (pin "2") (pinfunction "S_2") (pintype "passive"))
      (node (ref "T5") (pin "2") (pinfunction "S_2") (pintype "passive"))
      (node (ref "T6") (pin "2") (pinfunction "S_2") (pintype "passive"))
      (node (ref "T7") (pin "2") (pinfunction "S_2") (pintype "passive"))
      (node (ref "U2") (pin "5") (pinfunction "GND_5") (pintype "bidirectional"))
      (node (ref "U3") (pin "H3") (pinfunction "H-_H3") (pintype "bidirectional"))
      (node (ref "U3") (pin "V3") (pinfunction "V-_V3") (pintype "bidirectional"))
      (node (ref "U4") (pin "10") (pinfunction "GND_10") (pintype "bidirectional"))
      (node (ref "U5") (pin "P$22") (pinfunction "GND_P$22") (pintype "bidirectional"))
      (node (ref "U5") (pin "P$53") (pinfunction "GND_P$53") (pintype "bidirectional"))
      (node (ref "U5") (pin "P$63") (pinfunction "GND_P$63") (pintype "bidirectional"))
      (node (ref "U6") (pin "P$12") (pinfunction "GND_P$12") (pintype "bidirectional"))
      (node (ref "V1") (pin "2") (pinfunction "GND_2") (pintype "bidirectional"))
    )
    (net (code "35") (name "GREEN") (class "Default")
      (node (ref "CON16") (pin "1") (pinfunction "1_1") (pintype "bidirectional"))
      (node (ref "R22") (pin "1") (pinfunction "1_1") (pintype "passive"))
      (node (ref "T5") (pin "3") (pinfunction "D_3") (pintype "passive"))
    )
    (net (code "36") (name "HOLD") (class "Default")
      (node (ref "U4") (pin "1") (pinfunction "HOLD#/SIO3_1") (pintype "bidirectional"))
      (node (ref "U5") (pin "P$15") (pinfunction "PB5(OC1A/PCINT5)_P$15") (pintype "bidirectional"))
    )
    (net (code "37") (name "HORIZONTAL") (class "Default")
      (node (ref "U3") (pin "H2") (pinfunction "H_H2") (pintype "bidirectional"))
      (node (ref "U5") (pin "P$61") (pinfunction "PF0(ADC0)_P$61") (pintype "bidirectional"))
    )
    (net (code "38") (name "LED1") (class "Default")
      (node (ref "R26") (pin "1") (pinfunction "1_1") (pintype "passive"))
      (node (ref "U5") (pin "P$39") (pinfunction "PC4(A12)_P$39") (pintype "bidirectional"))
    )
    (net (code "39") (name "LED2") (class "Default")
      (node (ref "R29") (pin "1") (pinfunction "1_1") (pintype "passive"))
      (node (ref "U5") (pin "P$38") (pinfunction "PC3(A11)_P$38") (pintype "bidirectional"))
    )
    (net (code "40") (name "LED3") (class "Default")
      (node (ref "R30") (pin "1") (pinfunction "1_1") (pintype "passive"))
      (node (ref "U5") (pin "P$37") (pinfunction "PC2(A10)_P$37") (pintype "bidirectional"))
    )
    (net (code "41") (name "LED4") (class "Default")
      (node (ref "R34") (pin "2") (pinfunction "2_2") (pintype "passive"))
      (node (ref "U5") (pin "P$7") (pinfunction "PE5(OC3C/INT5)_P$7") (pintype "bidirectional"))
    )
    (net (code "42") (name "LED5") (class "Default")
      (node (ref "R35") (pin "2") (pinfunction "2_2") (pintype "passive"))
      (node (ref "U5") (pin "P$34") (pinfunction "PG1(~{RD})_P$34") (pintype "bidirectional"))
    )
    (net (code "43") (name "LED6") (class "Default")
      (node (ref "R32") (pin "2") (pinfunction "2_2") (pintype "passive"))
      (node (ref "U5") (pin "P$35") (pinfunction "PC0(A8)_P$35") (pintype "bidirectional"))
    )
    (net (code "44") (name "LED7") (class "Default")
      (node (ref "R33") (pin "2") (pinfunction "2_2") (pintype "passive"))
      (node (ref "U5") (pin "P$49") (pinfunction "PA2(AD2)_P$49") (pintype "bidirectional"))
    )
    (net (code "45") (name "MISO") (class "Default")
      (node (ref "CON1") (pin "6") (pinfunction "MISO_6") (pintype "bidirectional"))
      (node (ref "U4") (pin "8") (pinfunction "SO/SIO1_8") (pintype "bidirectional"))
      (node (ref "U5") (pin "P$13") (pinfunction "PB3(MISO/PCINT3)_P$13") (pintype "bidirectional"))
    )
    (net (code "46") (name "MOSI") (class "Default")
      (node (ref "CON1") (pin "2") (pinfunction "MOSI_2") (pintype "bidirectional"))
      (node (ref "U4") (pin "15") (pinfunction "SI/SIO0_15") (pintype "bidirectional"))
      (node (ref "U5") (pin "P$12") (pinfunction "PB2(MOSI/PCINT2)_P$12") (pintype "bidirectional"))
    )
    (net (code "47") (name "Net-(B1--)") (class "Default")
      (node (ref "B1") (pin "2") (pinfunction "-_2") (pintype "bidirectional"))
      (node (ref "R8") (pin "1") (pinfunction "1_1") (pintype "passive"))
      (node (ref "T1") (pin "3") (pinfunction "D_3") (pintype "passive"))
    )
    (net (code "48") (name "Net-(CON3-Pad4)") (class "Default")
      (node (ref "CON3") (pin "4") (pinfunction "4_4") (pintype "bidirectional"))
      (node (ref "R37") (pin "2") (pinfunction "2_2") (pintype "passive"))
    )
    (net (code "49") (name "Net-(CON4-Pad4)") (class "Default")
      (node (ref "CON4") (pin "4") (pinfunction "4_4") (pintype "bidirectional"))
      (node (ref "R38") (pin "2") (pinfunction "2_2") (pintype "passive"))
    )
    (net (code "50") (name "Net-(CON5-Pad4)") (class "Default")
      (node (ref "CON5") (pin "4") (pinfunction "4_4") (pintype "bidirectional"))
      (node (ref "R39") (pin "2") (pinfunction "2_2") (pintype "passive"))
    )
    (net (code "51") (name "Net-(CON6-Pad4)") (class "Default")
      (node (ref "CON6") (pin "4") (pinfunction "4_4") (pintype "bidirectional"))
      (node (ref "R40") (pin "2") (pinfunction "2_2") (pintype "passive"))
    )
    (net (code "52") (name "Net-(CON7-Pad4)") (class "Default")
      (node (ref "CON7") (pin "4") (pinfunction "4_4") (pintype "bidirectional"))
      (node (ref "R41") (pin "2") (pinfunction "2_2") (pintype "passive"))
    )
    (net (code "53") (name "Net-(CON8-Pad4)") (class "Default")
      (node (ref "CON8") (pin "4") (pinfunction "4_4") (pintype "bidirectional"))
      (node (ref "R42") (pin "2") (pinfunction "2_2") (pintype "passive"))
    )
    (net (code "54") (name "Net-(CON15-Pad1)") (class "Default")
      (node (ref "CON15") (pin "1") (pinfunction "1_1") (pintype "bidirectional"))
      (node (ref "R16") (pin "1") (pinfunction "1_1") (pintype "passive"))
    )
    (net (code "55") (name "Net-(CON19-Pad4)") (class "Default")
      (node (ref "CON19") (pin "4") (pinfunction "4_4") (pintype "bidirectional"))
      (node (ref "R2") (pin "2") (pinfunction "2_2") (pintype "passive"))
    )
    (net (code "56") (name "Net-(CON20-Pad4)") (class "Default")
      (node (ref "CON20") (pin "4") (pinfunction "4_4") (pintype "bidirectional"))
      (node (ref "R3") (pin "2") (pinfunction "2_2") (pintype "passive"))
    )
    (net (code "57") (name "Net-(CON21-Pad4)") (class "Default")
      (node (ref "CON21") (pin "4") (pinfunction "4_4") (pintype "bidirectional"))
      (node (ref "R4") (pin "2") (pinfunction "2_2") (pintype "passive"))
    )
    (net (code "58") (name "Net-(CON22-Pad4)") (class "Default")
      (node (ref "CON22") (pin "4") (pinfunction "4_4") (pintype "bidirectional"))
      (node (ref "R5") (pin "2") (pinfunction "2_2") (pintype "passive"))
    )
    (net (code "59") (name "Net-(CON23-Pad4)") (class "Default")
      (node (ref "CON23") (pin "4") (pinfunction "4_4") (pintype "bidirectional"))
      (node (ref "R6") (pin "2") (pinfunction "2_2") (pintype "passive"))
    )
    (net (code "60") (name "Net-(CON24-Pad4)") (class "Default")
      (node (ref "CON24") (pin "4") (pinfunction "4_4") (pintype "bidirectional"))
      (node (ref "R9") (pin "2") (pinfunction "2_2") (pintype "passive"))
    )
    (net (code "61") (name "Net-(CON25-Pad4)") (class "Default")
      (node (ref "CON25") (pin "4") (pinfunction "4_4") (pintype "bidirectional"))
      (node (ref "R17") (pin "2") (pinfunction "2_2") (pintype "passive"))
    )
    (net (code "62") (name "Net-(CON26-Pad4)") (class "Default")
      (node (ref "CON26") (pin "4") (pinfunction "4_4") (pintype "bidirectional"))
      (node (ref "R18") (pin "2") (pinfunction "2_2") (pintype "passive"))
    )
    (net (code "63") (name "Net-(CON27-Pad4)") (class "Default")
      (node (ref "CON27") (pin "4") (pinfunction "4_4") (pintype "bidirectional"))
      (node (ref "R19") (pin "2") (pinfunction "2_2") (pintype "passive"))
    )
    (net (code "64") (name "Net-(CON28-Pad4)") (class "Default")
      (node (ref "CON28") (pin "4") (pinfunction "4_4") (pintype "bidirectional"))
      (node (ref "R20") (pin "2") (pinfunction "2_2") (pintype "passive"))
    )
    (net (code "65") (name "Net-(LED1-BLUECATHODE)") (class "Default")
      (node (ref "LED1") (pin "3") (pinfunction "BLUECATHODE_3") (pintype "passive"))
      (node (ref "R21") (pin "2") (pinfunction "2_2") (pintype "passive"))
    )
    (net (code "66") (name "Net-(LED1-GREENCATHODE)") (class "Default")
      (node (ref "LED1") (pin "4") (pinfunction "GREENCATHODE_4") (pintype "passive"))
      (node (ref "R22") (pin "2") (pinfunction "2_2") (pintype "passive"))
    )
    (net (code "67") (name "Net-(LED1-REDCATHODE)") (class "Default")
      (node (ref "LED1") (pin "1") (pinfunction "REDCATHODE_1") (pintype "passive"))
      (node (ref "R1") (pin "2") (pinfunction "2_2") (pintype "passive"))
    )
    (net (code "68") (name "Net-(LED2-A)") (class "Default")
      (node (ref "C12") (pin "1") (pinfunction "1_1") (pintype "passive"))
      (node (ref "C2") (pin "1") (pinfunction "1_1") (pintype "passive"))
      (node (ref "C6") (pin "1") (pinfunction "1_1") (pintype "passive"))
      (node (ref "C7") (pin "1") (pinfunction "1_1") (pintype "passive"))
      (node (ref "C8") (pin "1") (pinfunction "1_1") (pintype "passive"))
      (node (ref "C9") (pin "1") (pinfunction "1_1") (pintype "passive"))
      (node (ref "CON15") (pin "2") (pinfunction "2_2") (pintype "bidirectional"))
      (node (ref "LED2") (pin "1") (pinfunction "A_1") (pintype "passive"))
      (node (ref "LED3") (pin "1") (pinfunction "A_1") (pintype "passive"))
      (node (ref "LED4") (pin "1") (pinfunction "A_1") (pintype "passive"))
      (node (ref "LED5") (pin "1") (pinfunction "A_1") (pintype "passive"))
      (node (ref "LED6") (pin "1") (pinfunction "A_1") (pintype "passive"))
      (node (ref "LED7") (pin "1") (pinfunction "A_1") (pintype "passive"))
    )
    (net (code "69") (name "Net-(LED2-C)") (class "Default")
      (node (ref "LED2") (pin "2") (pinfunction "C_2") (pintype "passive"))
      (node (ref "R10") (pin "2") (pinfunction "2_2") (pintype "passive"))
    )
    (net (code "70") (name "Net-(LED3-C)") (class "Default")
      (node (ref "LED3") (pin "2") (pinfunction "C_2") (pintype "passive"))
      (node (ref "R11") (pin "2") (pinfunction "2_2") (pintype "passive"))
    )
    (net (code "71") (name "Net-(LED4-C)") (class "Default")
      (node (ref "LED4") (pin "2") (pinfunction "C_2") (pintype "passive"))
      (node (ref "R12") (pin "2") (pinfunction "2_2") (pintype "passive"))
    )
    (net (code "72") (name "Net-(LED5-C)") (class "Default")
      (node (ref "LED5") (pin "2") (pinfunction "C_2") (pintype "passive"))
      (node (ref "R13") (pin "2") (pinfunction "2_2") (pintype "passive"))
    )
    (net (code "73") (name "Net-(LED6-C)") (class "Default")
      (node (ref "LED6") (pin "2") (pinfunction "C_2") (pintype "passive"))
      (node (ref "R14") (pin "2") (pinfunction "2_2") (pintype "passive"))
    )
    (net (code "74") (name "Net-(LED7-C)") (class "Default")
      (node (ref "LED7") (pin "2") (pinfunction "C_2") (pintype "passive"))
      (node (ref "R25") (pin "2") (pinfunction "2_2") (pintype "passive"))
    )
    (net (code "75") (name "Net-(LED8-C)") (class "Default")
      (node (ref "LED8") (pin "1") (pinfunction "C_1") (pintype "passive"))
      (node (ref "R32") (pin "1") (pinfunction "1_1") (pintype "passive"))
    )
    (net (code "76") (name "Net-(LED9-C)") (class "Default")
      (node (ref "LED9") (pin "1") (pinfunction "C_1") (pintype "passive"))
      (node (ref "R33") (pin "1") (pinfunction "1_1") (pintype "passive"))
    )
    (net (code "77") (name "Net-(LED10-A)") (class "Default")
      (node (ref "LED10") (pin "2") (pinfunction "A_2") (pintype "passive"))
      (node (ref "T3") (pin "5") (pinfunction "D_5") (pintype "passive"))
      (node (ref "T3") (pin "6") (pinfunction "D_6") (pintype "passive"))
      (node (ref "T3") (pin "7") (pinfunction "D_7") (pintype "passive"))
      (node (ref "T3") (pin "8") (pinfunction "D_8") (pintype "passive"))
      (node (ref "U2") (pin "1") (pinfunction "IP+_1") (pintype "bidirectional"))
      (node (ref "U2") (pin "2") (pinfunction "IP+_2") (pintype "bidirectional"))
    )
    (net (code "78") (name "Net-(LED10-C)") (class "Default")
      (node (ref "LED10") (pin "1") (pinfunction "C_1") (pintype "passive"))
      (node (ref "R27") (pin "2") (pinfunction "2_2") (pintype "passive"))
    )
    (net (code "79") (name "Net-(LED11-C)") (class "Default")
      (node (ref "LED11") (pin "1") (pinfunction "C_1") (pintype "passive"))
      (node (ref "R34") (pin "1") (pinfunction "1_1") (pintype "passive"))
    )
    (net (code "80") (name "Net-(LED12-C)") (class "Default")
      (node (ref "LED12") (pin "1") (pinfunction "C_1") (pintype "passive"))
      (node (ref "R35") (pin "1") (pinfunction "1_1") (pintype "passive"))
    )
    (net (code "81") (name "Net-(LED13-C)") (class "Default")
      (node (ref "LED13") (pin "1") (pinfunction "C_1") (pintype "passive"))
      (node (ref "R36") (pin "1") (pinfunction "1_1") (pintype "passive"))
    )
    (net (code "82") (name "Net-(T1-G)") (class "Default")
      (node (ref "R28") (pin "2") (pinfunction "2_2") (pintype "passive"))
      (node (ref "T1") (pin "1") (pinfunction "G_1") (pintype "passive"))
    )
    (net (code "83") (name "Net-(T2-D)") (class "Default")
      (node (ref "R10") (pin "1") (pinfunction "1_1") (pintype "passive"))
      (node (ref "R11") (pin "1") (pinfunction "1_1") (pintype "passive"))
      (node (ref "R12") (pin "1") (pinfunction "1_1") (pintype "passive"))
      (node (ref "R13") (pin "1") (pinfunction "1_1") (pintype "passive"))
      (node (ref "R14") (pin "1") (pinfunction "1_1") (pintype "passive"))
      (node (ref "R25") (pin "1") (pinfunction "1_1") (pintype "passive"))
      (node (ref "T2") (pin "3") (pinfunction "D_3") (pintype "passive"))
    )
    (net (code "84") (name "Net-(T2-G)") (class "Default")
      (node (ref "R16") (pin "2") (pinfunction "2_2") (pintype "passive"))
      (node (ref "T2") (pin "1") (pinfunction "G_1") (pintype "passive"))
    )
    (net (code "85") (name "Net-(T2-S)") (class "Default")
      (node (ref "C12") (pin "2") (pinfunction "2_2") (pintype "passive"))
      (node (ref "C2") (pin "2") (pinfunction "2_2") (pintype "passive"))
      (node (ref "C6") (pin "2") (pinfunction "2_2") (pintype "passive"))
      (node (ref "C7") (pin "2") (pinfunction "2_2") (pintype "passive"))
      (node (ref "C8") (pin "2") (pinfunction "2_2") (pintype "passive"))
      (node (ref "C9") (pin "2") (pinfunction "2_2") (pintype "passive"))
      (node (ref "CON15") (pin "3") (pinfunction "3_3") (pintype "bidirectional"))
      (node (ref "T2") (pin "2") (pinfunction "S_2") (pintype "passive"))
    )
    (net (code "86") (name "Net-(T3-G)") (class "Default")
      (node (ref "R24") (pin "1") (pinfunction "1_1") (pintype "passive"))
      (node (ref "T3") (pin "4") (pinfunction "G_4") (pintype "passive"))
      (node (ref "T7") (pin "3") (pinfunction "D_3") (pintype "passive"))
    )
    (net (code "87") (name "Net-(T4-G)") (class "Default")
      (node (ref "R26") (pin "2") (pinfunction "2_2") (pintype "passive"))
      (node (ref "T4") (pin "1") (pinfunction "G_1") (pintype "passive"))
    )
    (net (code "88") (name "Net-(T5-G)") (class "Default")
      (node (ref "R29") (pin "2") (pinfunction "2_2") (pintype "passive"))
      (node (ref "T5") (pin "1") (pinfunction "G_1") (pintype "passive"))
    )
    (net (code "89") (name "Net-(T6-G)") (class "Default")
      (node (ref "R30") (pin "2") (pinfunction "2_2") (pintype "passive"))
      (node (ref "T6") (pin "1") (pinfunction "G_1") (pintype "passive"))
    )
    (net (code "90") (name "Net-(T7-G)") (class "Default")
      (node (ref "R31") (pin "1") (pinfunction "1_1") (pintype "passive"))
      (node (ref "T7") (pin "1") (pinfunction "G_1") (pintype "passive"))
    )
    (net (code "91") (name "Net-(U$3-A)") (class "Default")
      (node (ref "U$3") (pin "1") (pinfunction "A_1") (pintype "passive"))
      (node (ref "U$4") (pin "1") (pinfunction "A_1") (pintype "passive"))
      (node (ref "U2") (pin "3") (pinfunction "IP-_3") (pintype "bidirectional"))
      (node (ref "U2") (pin "4") (pinfunction "IP-_4") (pintype "bidirectional"))
    )
    (net (code "92") (name "Net-(U5-PD0(SCL{slash}INT0))") (class "Default")
      (node (ref "CON13") (pin "2") (pinfunction "2_2") (pintype "bidirectional"))
      (node (ref "U5") (pin "P$25") (pinfunction "PD0(SCL/INT0)_P$25") (pintype "bidirectional"))
    )
    (net (code "93") (name "Net-(U5-PD1(SDA{slash}INT1))") (class "Default")
      (node (ref "CON13") (pin "3") (pinfunction "3_3") (pintype "bidirectional"))
      (node (ref "U5") (pin "P$26") (pinfunction "PD1(SDA/INT1)_P$26") (pintype "bidirectional"))
    )
    (net (code "94") (name "Net-(U5-PD2(RXD1{slash}INT2))") (class "Default")
      (node (ref "CON17") (pin "2") (pinfunction "2_2") (pintype "bidirectional"))
      (node (ref "U5") (pin "P$27") (pinfunction "PD2(RXD1/INT2)_P$27") (pintype "bidirectional"))
    )
    (net (code "95") (name "Net-(U5-PD3(TXD1{slash}INT3))") (class "Default")
      (node (ref "CON17") (pin "3") (pinfunction "3_3") (pintype "bidirectional"))
      (node (ref "U5") (pin "P$28") (pinfunction "PD3(TXD1/INT3)_P$28") (pintype "bidirectional"))
    )
    (net (code "96") (name "Net-(U5-XTAL1)") (class "Default")
      (node (ref "C23") (pin "1") (pinfunction "1_1") (pintype "passive"))
      (node (ref "U5") (pin "P$24") (pinfunction "XTAL1_P$24") (pintype "bidirectional"))
      (node (ref "XTAL2") (pin "1") (pinfunction "1_1") (pintype "passive"))
    )
    (net (code "97") (name "Net-(U5-XTAL2)") (class "Default")
      (node (ref "C22") (pin "1") (pinfunction "1_1") (pintype "passive"))
      (node (ref "U5") (pin "P$23") (pinfunction "XTAL2_P$23") (pintype "bidirectional"))
      (node (ref "XTAL2") (pin "2") (pinfunction "2_2") (pintype "passive"))
    )
    (net (code "98") (name "Net-(U6-~{E2})") (class "Default")
      (node (ref "R43") (pin "1") (pinfunction "1_1") (pintype "passive"))
      (node (ref "U6") (pin "P$19") (pinfunction "~{E2}_P$19") (pintype "bidirectional"))
    )
    (net (code "99") (name "RED") (class "Default")
      (node (ref "CON16") (pin "3") (pinfunction "3_3") (pintype "bidirectional"))
      (node (ref "R1") (pin "1") (pinfunction "1_1") (pintype "passive"))
      (node (ref "T6") (pin "3") (pinfunction "D_3") (pintype "passive"))
    )
    (net (code "100") (name "RESET") (class "Default")
      (node (ref "C14") (pin "1") (pinfunction "1_1") (pintype "passive"))
      (node (ref "CON1") (pin "4") (pinfunction "~{RESET}_4") (pintype "bidirectional"))
      (node (ref "R7") (pin "2") (pinfunction "2_2") (pintype "passive"))
      (node (ref "S1") (pin "3") (pinfunction "P_3") (pintype "passive"))
      (node (ref "S1") (pin "4") (pinfunction "P1_4") (pintype "passive"))
      (node (ref "U5") (pin "P$20") (pinfunction "~{RESET}_P$20") (pintype "bidirectional"))
    )
    (net (code "101") (name "SCK") (class "Default")
      (node (ref "CON1") (pin "5") (pinfunction "SCK_5") (pintype "bidirectional"))
      (node (ref "U4") (pin "16") (pinfunction "SCLK_16") (pintype "bidirectional"))
      (node (ref "U5") (pin "P$11") (pinfunction "PB1(SCK/PCINT1)_P$11") (pintype "bidirectional"))
    )
    (net (code "102") (name "TRANSMITLEDS") (class "Default")
      (node (ref "CON14") (pin "1") (pinfunction "1_1") (pintype "bidirectional"))
      (node (ref "U5") (pin "P$10") (pinfunction "PB0(~{SS}/PCINT0)_P$10") (pintype "bidirectional"))
    )
    (net (code "103") (name "VERTICAL") (class "Default")
      (node (ref "U3") (pin "V2") (pinfunction "V_V2") (pintype "bidirectional"))
      (node (ref "U5") (pin "P$60") (pinfunction "PF1(ADC1)_P$60") (pintype "bidirectional"))
    )
    (net (code "104") (name "WP") (class "Default")
      (node (ref "U4") (pin "9") (pinfunction "WP#/SIO2_9") (pintype "bidirectional"))
      (node (ref "U5") (pin "P$14") (pinfunction "PB4(OC2A/PCINT4)_P$14") (pintype "bidirectional"))
    )
    (net (code "105") (name "unconnected-(U2-~{FAULT}-Pad6)") (class "Default")
      (node (ref "U2") (pin "6") (pinfunction "~{FAULT}_6") (pintype "bidirectional"))
    )
    (net (code "106") (name "unconnected-(U5-PA0(AD0)-PadP$51)") (class "Default")
      (node (ref "U5") (pin "P$51") (pinfunction "PA0(AD0)_P$51") (pintype "bidirectional"))
    )
    (net (code "107") (name "unconnected-(U5-PA1(AD1)-PadP$50)") (class "Default")
      (node (ref "U5") (pin "P$50") (pinfunction "PA1(AD1)_P$50") (pintype "bidirectional"))
    )
    (net (code "108") (name "unconnected-(U5-PA3(AD3)-PadP$48)") (class "Default")
      (node (ref "U5") (pin "P$48") (pinfunction "PA3(AD3)_P$48") (pintype "bidirectional"))
    )
    (net (code "109") (name "unconnected-(U5-PA4(AD4)-PadP$47)") (class "Default")
      (node (ref "U5") (pin "P$47") (pinfunction "PA4(AD4)_P$47") (pintype "bidirectional"))
    )
    (net (code "110") (name "unconnected-(U5-PA5(AD5)-PadP$46)") (class "Default")
      (node (ref "U5") (pin "P$46") (pinfunction "PA5(AD5)_P$46") (pintype "bidirectional"))
    )
    (net (code "111") (name "unconnected-(U5-PA6(AD6)-PadP$45)") (class "Default")
      (node (ref "U5") (pin "P$45") (pinfunction "PA6(AD6)_P$45") (pintype "bidirectional"))
    )
    (net (code "112") (name "unconnected-(U5-PC1(A9)-PadP$36)") (class "Default")
      (node (ref "U5") (pin "P$36") (pinfunction "PC1(A9)_P$36") (pintype "bidirectional"))
    )
    (net (code "113") (name "unconnected-(U5-PC5(A13)-PadP$40)") (class "Default")
      (node (ref "U5") (pin "P$40") (pinfunction "PC5(A13)_P$40") (pintype "bidirectional"))
    )
    (net (code "114") (name "unconnected-(U5-PC6(A14)-PadP$41)") (class "Default")
      (node (ref "U5") (pin "P$41") (pinfunction "PC6(A14)_P$41") (pintype "bidirectional"))
    )
    (net (code "115") (name "unconnected-(U5-PC7(A15)-PadP$42)") (class "Default")
      (node (ref "U5") (pin "P$42") (pinfunction "PC7(A15)_P$42") (pintype "bidirectional"))
    )
    (net (code "116") (name "unconnected-(U5-PD4(ICP1)-PadP$29)") (class "Default")
      (node (ref "U5") (pin "P$29") (pinfunction "PD4(ICP1)_P$29") (pintype "bidirectional"))
    )
    (net (code "117") (name "unconnected-(U5-PD5(XCK1)-PadP$30)") (class "Default")
      (node (ref "U5") (pin "P$30") (pinfunction "PD5(XCK1)_P$30") (pintype "bidirectional"))
    )
    (net (code "118") (name "unconnected-(U5-PD6(T1)-PadP$31)") (class "Default")
      (node (ref "U5") (pin "P$31") (pinfunction "PD6(T1)_P$31") (pintype "bidirectional"))
    )
    (net (code "119") (name "unconnected-(U5-PD7(T0)-PadP$32)") (class "Default")
      (node (ref "U5") (pin "P$32") (pinfunction "PD7(T0)_P$32") (pintype "bidirectional"))
    )
    (net (code "120") (name "unconnected-(U5-PE2(XCK0{slash}AIN0)-PadP$4)") (class "Default")
      (node (ref "U5") (pin "P$4") (pinfunction "PE2(XCK0/AIN0)_P$4") (pintype "bidirectional"))
    )
    (net (code "121") (name "unconnected-(U5-PE3(OC3A{slash}AIN1)-PadP$5)") (class "Default")
      (node (ref "U5") (pin "P$5") (pinfunction "PE3(OC3A/AIN1)_P$5") (pintype "bidirectional"))
    )
    (net (code "122") (name "unconnected-(U5-PE4(OC3B{slash}INT4)-PadP$6)") (class "Default")
      (node (ref "U5") (pin "P$6") (pinfunction "PE4(OC3B/INT4)_P$6") (pintype "bidirectional"))
    )
    (net (code "123") (name "unconnected-(U5-PE6(T3{slash}INT6)-PadP$8)") (class "Default")
      (node (ref "U5") (pin "P$8") (pinfunction "PE6(T3/INT6)_P$8") (pintype "bidirectional"))
    )
    (net (code "124") (name "unconnected-(U5-PF3(ADC3)-PadP$58)") (class "Default")
      (node (ref "U5") (pin "P$58") (pinfunction "PF3(ADC3)_P$58") (pintype "bidirectional"))
    )
    (net (code "125") (name "unconnected-(U5-PF4(ADC4{slash}TCK)-PadP$57)") (class "Default")
      (node (ref "U5") (pin "P$57") (pinfunction "PF4(ADC4/TCK)_P$57") (pintype "bidirectional"))
    )
    (net (code "126") (name "unconnected-(U5-PF5(ADC5{slash}TMS)-PadP$56)") (class "Default")
      (node (ref "U5") (pin "P$56") (pinfunction "PF5(ADC5/TMS)_P$56") (pintype "bidirectional"))
    )
    (net (code "127") (name "unconnected-(U5-PF6(ADC6{slash}TDO)-PadP$55)") (class "Default")
      (node (ref "U5") (pin "P$55") (pinfunction "PF6(ADC6/TDO)_P$55") (pintype "bidirectional"))
    )
    (net (code "128") (name "unconnected-(U5-PF7(ADC7{slash}TDI)-PadP$54)") (class "Default")
      (node (ref "U5") (pin "P$54") (pinfunction "PF7(ADC7/TDI)_P$54") (pintype "bidirectional"))
    )
  )
)
